# RingMod.net
KiCad netlist of a schematic drawn in EAGLE
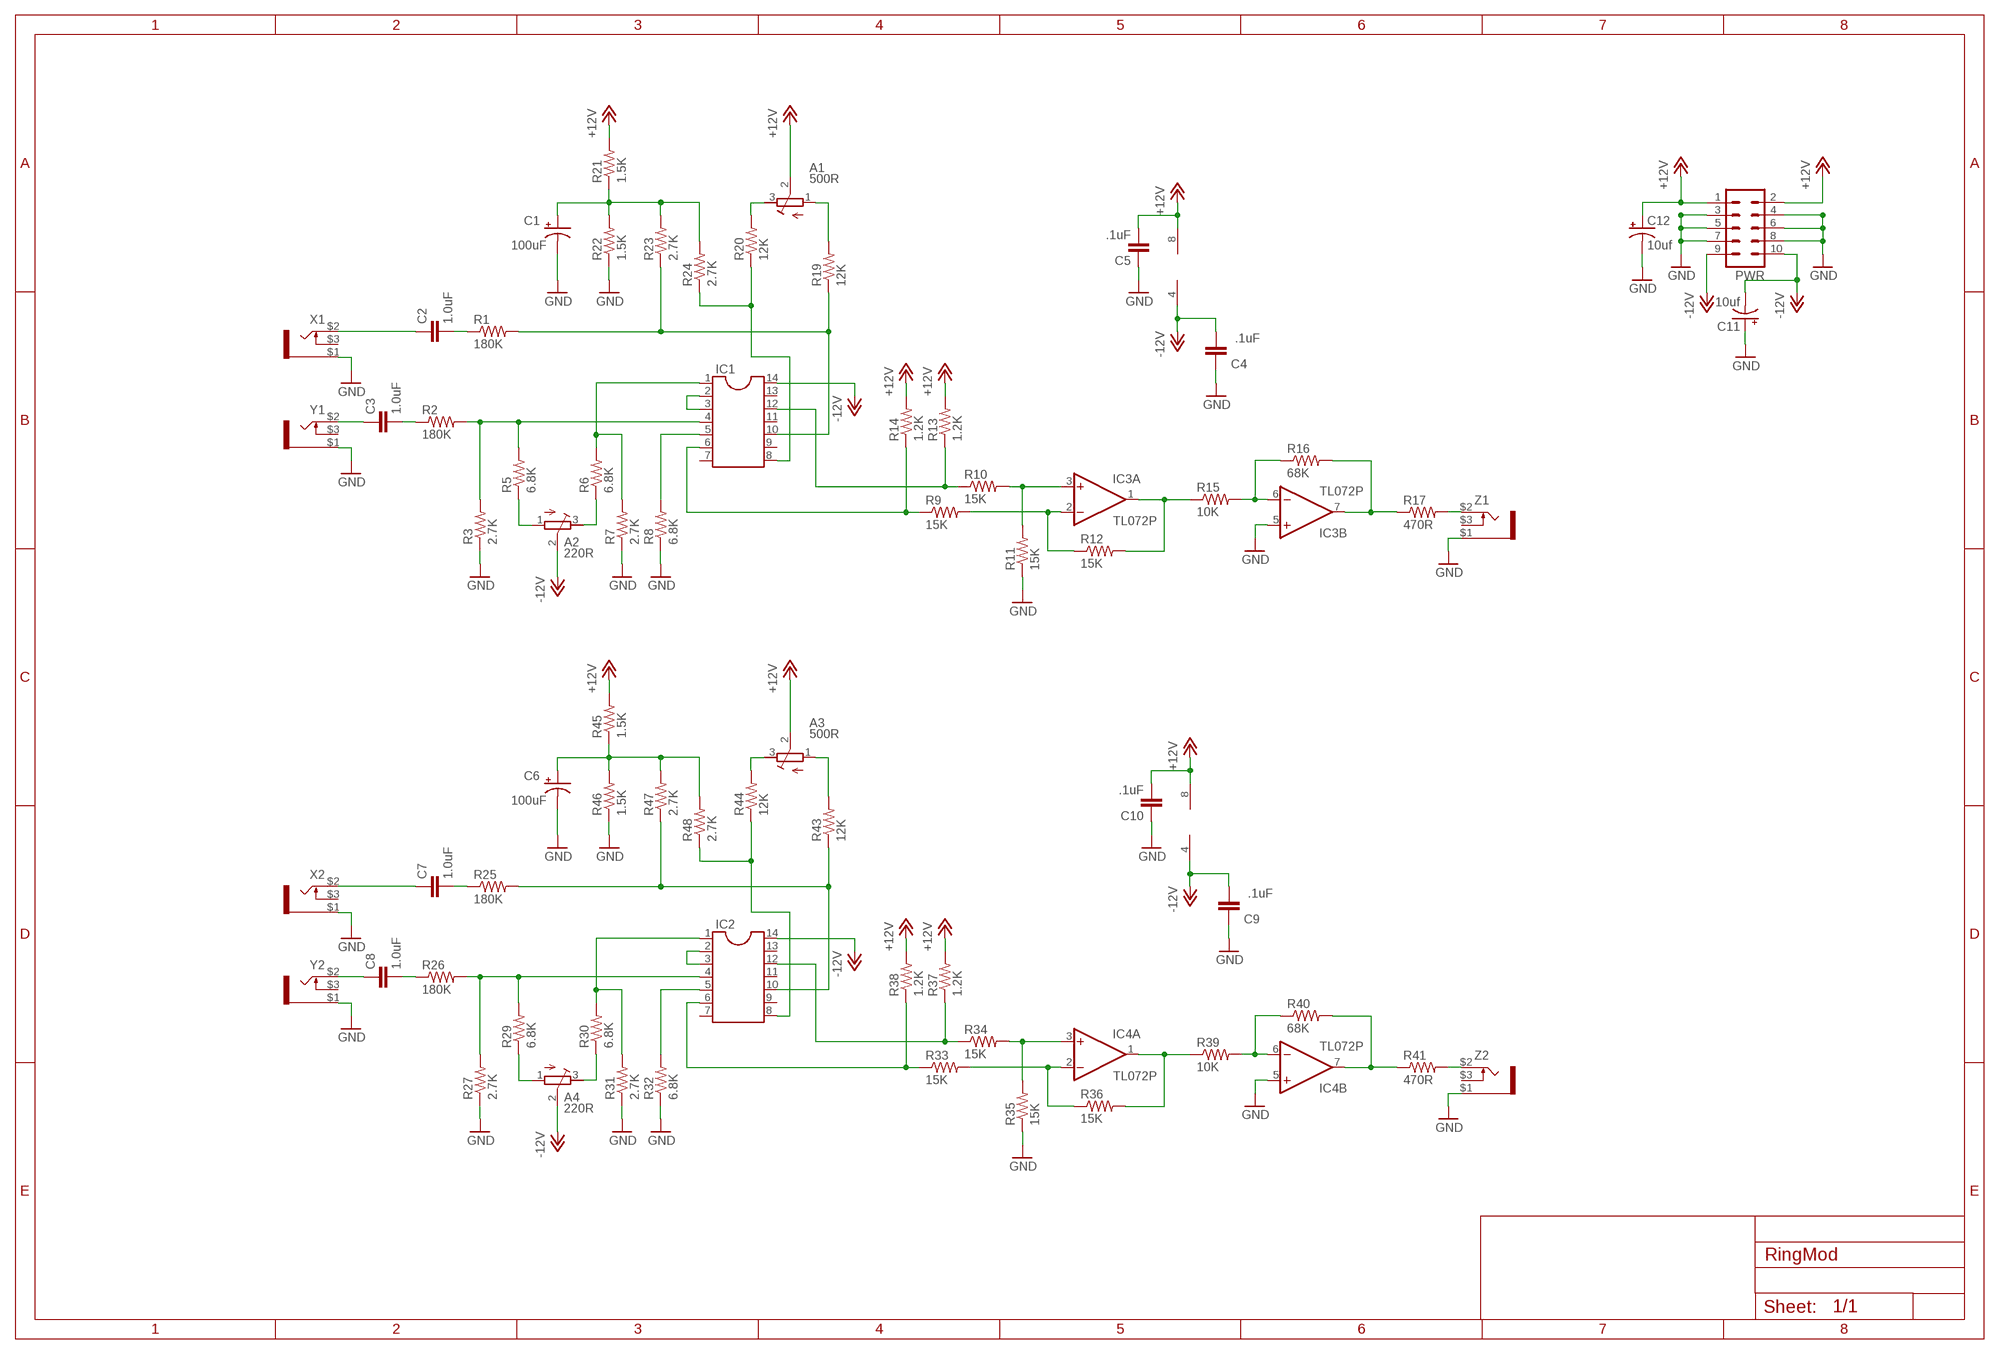
[diagram p0: schematic, sheet 1]

(export (version "E")
  (design (tool "Eeschema 10.0.6"))
  (components
    (comp (ref "A1")
      (value "500R")
      (footprint "eagle-import:RTRIM3296W")
      (libsource (lib "eagle-import") (part "R-TRIMM3296W"))
    )
    (comp (ref "A2")
      (value "220R")
      (footprint "eagle-import:RTRIM3296W")
      (libsource (lib "eagle-import") (part "R-TRIMM3296W"))
    )
    (comp (ref "A3")
      (value "500R")
      (footprint "eagle-import:RTRIM3296W")
      (libsource (lib "eagle-import") (part "R-TRIMM3296W"))
    )
    (comp (ref "A4")
      (value "220R")
      (footprint "eagle-import:RTRIM3296W")
      (libsource (lib "eagle-import") (part "R-TRIMM3296W"))
    )
    (comp (ref "C1")
      (value "100uF")
      (footprint "eagle-import:E2,5-6")
      (libsource (lib "eagle-import") (part "resistor_348_CPOL-USE2.5-6"))
    )
    (comp (ref "C2")
      (value "1.0uF")
      (footprint "eagle-import:C050-024X044")
      (libsource (lib "eagle-import") (part "C-EU050-024X044"))
    )
    (comp (ref "C3")
      (value "1.0uF")
      (footprint "eagle-import:C050-024X044")
      (libsource (lib "eagle-import") (part "C-EU050-024X044"))
    )
    (comp (ref "C4")
      (value ".1uF")
      (footprint "eagle-import:C050-024X044")
      (libsource (lib "eagle-import") (part "C-EU050-024X044"))
    )
    (comp (ref "C5")
      (value ".1uF")
      (footprint "eagle-import:C050-024X044")
      (libsource (lib "eagle-import") (part "C-EU050-024X044"))
    )
    (comp (ref "C6")
      (value "100uF")
      (footprint "eagle-import:E2,5-6")
      (libsource (lib "eagle-import") (part "resistor_348_CPOL-USE2.5-6"))
    )
    (comp (ref "C7")
      (value "1.0uF")
      (footprint "eagle-import:C050-024X044")
      (libsource (lib "eagle-import") (part "C-EU050-024X044"))
    )
    (comp (ref "C8")
      (value "1.0uF")
      (footprint "eagle-import:C050-024X044")
      (libsource (lib "eagle-import") (part "C-EU050-024X044"))
    )
    (comp (ref "C9")
      (value ".1uF")
      (footprint "eagle-import:C050-024X044")
      (libsource (lib "eagle-import") (part "C-EU050-024X044"))
    )
    (comp (ref "C10")
      (value ".1uF")
      (footprint "eagle-import:C050-024X044")
      (libsource (lib "eagle-import") (part "C-EU050-024X044"))
    )
    (comp (ref "C11")
      (value "10uf")
      (footprint "eagle-import:E2,5-5")
      (libsource (lib "eagle-import") (part "CPOL-USE2.5-5"))
    )
    (comp (ref "C12")
      (value "10uf")
      (footprint "eagle-import:E2,5-5")
      (libsource (lib "eagle-import") (part "CPOL-USE2.5-5"))
    )
    (comp (ref "IC1")
      (value "LM1496")
      (footprint "eagle-import:LM1496")
      (libsource (lib "eagle-import") (part "LM1496"))
    )
    (comp (ref "IC2")
      (value "LM1496")
      (footprint "eagle-import:LM1496")
      (libsource (lib "eagle-import") (part "LM1496"))
    )
    (comp (ref "IC3")
      (value "TL072P")
      (footprint "eagle-import:DIL08")
      (libsource (lib "eagle-import") (part "TL072P"))
    )
    (comp (ref "IC4")
      (value "TL072P")
      (footprint "eagle-import:DIL08")
      (libsource (lib "eagle-import") (part "TL072P"))
    )
    (comp (ref "PWR")
      (value "ML10")
      (footprint "eagle-import:ML10")
      (libsource (lib "eagle-import") (part "ML10"))
    )
    (comp (ref "R1")
      (value "180K")
      (footprint "eagle-import:0207_7")
      (libsource (lib "eagle-import") (part "R-US_0207/7"))
    )
    (comp (ref "R2")
      (value "180K")
      (footprint "eagle-import:0207_7")
      (libsource (lib "eagle-import") (part "R-US_0207/7"))
    )
    (comp (ref "R3")
      (value "2.7K")
      (footprint "eagle-import:0207_7")
      (libsource (lib "eagle-import") (part "R-US_0207/7"))
    )
    (comp (ref "R5")
      (value "6.8K")
      (footprint "eagle-import:0207_7")
      (libsource (lib "eagle-import") (part "R-US_0207/7"))
    )
    (comp (ref "R6")
      (value "6.8K")
      (footprint "eagle-import:0207_7")
      (libsource (lib "eagle-import") (part "R-US_0207/7"))
    )
    (comp (ref "R7")
      (value "2.7K")
      (footprint "eagle-import:0207_7")
      (libsource (lib "eagle-import") (part "R-US_0207/7"))
    )
    (comp (ref "R8")
      (value "6.8K")
      (footprint "eagle-import:0207_7")
      (libsource (lib "eagle-import") (part "R-US_0207/7"))
    )
    (comp (ref "R9")
      (value "15K")
      (footprint "eagle-import:0207_7")
      (libsource (lib "eagle-import") (part "R-US_0207/7"))
    )
    (comp (ref "R10")
      (value "15K")
      (footprint "eagle-import:0207_7")
      (libsource (lib "eagle-import") (part "R-US_0207/7"))
    )
    (comp (ref "R11")
      (value "15K")
      (footprint "eagle-import:0207_7")
      (libsource (lib "eagle-import") (part "R-US_0207/7"))
    )
    (comp (ref "R12")
      (value "15K")
      (footprint "eagle-import:0207_7")
      (libsource (lib "eagle-import") (part "R-US_0207/7"))
    )
    (comp (ref "R13")
      (value "1.2K")
      (footprint "eagle-import:0207_7")
      (libsource (lib "eagle-import") (part "R-US_0207/7"))
    )
    (comp (ref "R14")
      (value "1.2K")
      (footprint "eagle-import:0207_7")
      (libsource (lib "eagle-import") (part "R-US_0207/7"))
    )
    (comp (ref "R15")
      (value "10K")
      (footprint "eagle-import:0207_7")
      (libsource (lib "eagle-import") (part "R-US_0207/7"))
    )
    (comp (ref "R16")
      (value "68K")
      (footprint "eagle-import:0207_7")
      (libsource (lib "eagle-import") (part "R-US_0207/7"))
    )
    (comp (ref "R17")
      (value "470R")
      (footprint "eagle-import:0207_7")
      (libsource (lib "eagle-import") (part "R-US_0207/7"))
    )
    (comp (ref "R19")
      (value "12K")
      (footprint "eagle-import:0207_7")
      (libsource (lib "eagle-import") (part "R-US_0207/7"))
    )
    (comp (ref "R20")
      (value "12K")
      (footprint "eagle-import:0207_7")
      (libsource (lib "eagle-import") (part "R-US_0207/7"))
    )
    (comp (ref "R21")
      (value "1.5K")
      (footprint "eagle-import:0207_7")
      (libsource (lib "eagle-import") (part "R-US_0207/7"))
    )
    (comp (ref "R22")
      (value "1.5K")
      (footprint "eagle-import:0207_7")
      (libsource (lib "eagle-import") (part "R-US_0207/7"))
    )
    (comp (ref "R23")
      (value "2.7K")
      (footprint "eagle-import:0207_7")
      (libsource (lib "eagle-import") (part "R-US_0207/7"))
    )
    (comp (ref "R24")
      (value "2.7K")
      (footprint "eagle-import:0207_7")
      (libsource (lib "eagle-import") (part "R-US_0207/7"))
    )
    (comp (ref "R25")
      (value "180K")
      (footprint "eagle-import:0207_7")
      (libsource (lib "eagle-import") (part "R-US_0207/7"))
    )
    (comp (ref "R26")
      (value "180K")
      (footprint "eagle-import:0207_7")
      (libsource (lib "eagle-import") (part "R-US_0207/7"))
    )
    (comp (ref "R27")
      (value "2.7K")
      (footprint "eagle-import:0207_7")
      (libsource (lib "eagle-import") (part "R-US_0207/7"))
    )
    (comp (ref "R29")
      (value "6.8K")
      (footprint "eagle-import:0207_7")
      (libsource (lib "eagle-import") (part "R-US_0207/7"))
    )
    (comp (ref "R30")
      (value "6.8K")
      (footprint "eagle-import:0207_7")
      (libsource (lib "eagle-import") (part "R-US_0207/7"))
    )
    (comp (ref "R31")
      (value "2.7K")
      (footprint "eagle-import:0207_7")
      (libsource (lib "eagle-import") (part "R-US_0207/7"))
    )
    (comp (ref "R32")
      (value "6.8K")
      (footprint "eagle-import:0207_7")
      (libsource (lib "eagle-import") (part "R-US_0207/7"))
    )
    (comp (ref "R33")
      (value "15K")
      (footprint "eagle-import:0207_7")
      (libsource (lib "eagle-import") (part "R-US_0207/7"))
    )
    (comp (ref "R34")
      (value "15K")
      (footprint "eagle-import:0207_7")
      (libsource (lib "eagle-import") (part "R-US_0207/7"))
    )
    (comp (ref "R35")
      (value "15K")
      (footprint "eagle-import:0207_7")
      (libsource (lib "eagle-import") (part "R-US_0207/7"))
    )
    (comp (ref "R36")
      (value "15K")
      (footprint "eagle-import:0207_7")
      (libsource (lib "eagle-import") (part "R-US_0207/7"))
    )
    (comp (ref "R37")
      (value "1.2K")
      (footprint "eagle-import:0207_7")
      (libsource (lib "eagle-import") (part "R-US_0207/7"))
    )
    (comp (ref "R38")
      (value "1.2K")
      (footprint "eagle-import:0207_7")
      (libsource (lib "eagle-import") (part "R-US_0207/7"))
    )
    (comp (ref "R39")
      (value "10K")
      (footprint "eagle-import:0207_7")
      (libsource (lib "eagle-import") (part "R-US_0207/7"))
    )
    (comp (ref "R40")
      (value "68K")
      (footprint "eagle-import:0207_7")
      (libsource (lib "eagle-import") (part "R-US_0207/7"))
    )
    (comp (ref "R41")
      (value "470R")
      (footprint "eagle-import:0207_7")
      (libsource (lib "eagle-import") (part "R-US_0207/7"))
    )
    (comp (ref "R43")
      (value "12K")
      (footprint "eagle-import:0207_7")
      (libsource (lib "eagle-import") (part "R-US_0207/7"))
    )
    (comp (ref "R44")
      (value "12K")
      (footprint "eagle-import:0207_7")
      (libsource (lib "eagle-import") (part "R-US_0207/7"))
    )
    (comp (ref "R45")
      (value "1.5K")
      (footprint "eagle-import:0207_7")
      (libsource (lib "eagle-import") (part "R-US_0207/7"))
    )
    (comp (ref "R46")
      (value "1.5K")
      (footprint "eagle-import:0207_7")
      (libsource (lib "eagle-import") (part "R-US_0207/7"))
    )
    (comp (ref "R47")
      (value "2.7K")
      (footprint "eagle-import:0207_7")
      (libsource (lib "eagle-import") (part "R-US_0207/7"))
    )
    (comp (ref "R48")
      (value "2.7K")
      (footprint "eagle-import:0207_7")
      (libsource (lib "eagle-import") (part "R-US_0207/7"))
    )
    (comp (ref "X1")
      (value "PJ-323PJ-323")
      (footprint "eagle-import:PJ-323")
      (libsource (lib "eagle-import") (part "PJ-323PJ-323"))
    )
    (comp (ref "X2")
      (value "PJ-323PJ-323")
      (footprint "eagle-import:PJ-323")
      (libsource (lib "eagle-import") (part "PJ-323PJ-323"))
    )
    (comp (ref "Y1")
      (value "PJ-323PJ-323")
      (footprint "eagle-import:PJ-323")
      (libsource (lib "eagle-import") (part "PJ-323PJ-323"))
    )
    (comp (ref "Y2")
      (value "PJ-323PJ-323")
      (footprint "eagle-import:PJ-323")
      (libsource (lib "eagle-import") (part "PJ-323PJ-323"))
    )
    (comp (ref "Z1")
      (value "PJ-323PJ-323")
      (footprint "eagle-import:PJ-323")
      (libsource (lib "eagle-import") (part "PJ-323PJ-323"))
    )
    (comp (ref "Z2")
      (value "PJ-323PJ-323")
      (footprint "eagle-import:PJ-323")
      (libsource (lib "eagle-import") (part "PJ-323PJ-323"))
    )
  )
  (nets
    (net (code "1") (name "+12V") (class "Default")
      (node (ref "A1") (pin "2") (pinfunction "S_2") (pintype "passive"))
      (node (ref "A3") (pin "2") (pinfunction "S_2") (pintype "passive"))
      (node (ref "C10") (pin "2") (pinfunction "2_2") (pintype "passive"))
      (node (ref "C12") (pin "+") (pinfunction "+_+") (pintype "passive"))
      (node (ref "C5") (pin "2") (pinfunction "2_2") (pintype "passive"))
      (node (ref "IC3") (pin "8") (pinfunction "V+_8") (pintype "power_in"))
      (node (ref "IC4") (pin "8") (pinfunction "V+_8") (pintype "power_in"))
      (node (ref "PWR") (pin "1") (pinfunction "1_1") (pintype "passive"))
      (node (ref "PWR") (pin "2") (pinfunction "2_2") (pintype "passive"))
      (node (ref "R13") (pin "2") (pinfunction "2_2") (pintype "passive"))
      (node (ref "R14") (pin "2") (pinfunction "2_2") (pintype "passive"))
      (node (ref "R21") (pin "2") (pinfunction "2_2") (pintype "passive"))
      (node (ref "R37") (pin "2") (pinfunction "2_2") (pintype "passive"))
      (node (ref "R38") (pin "2") (pinfunction "2_2") (pintype "passive"))
      (node (ref "R45") (pin "2") (pinfunction "2_2") (pintype "passive"))
    )
    (net (code "2") (name "-12V") (class "Default")
      (node (ref "A2") (pin "2") (pinfunction "S_2") (pintype "passive"))
      (node (ref "A4") (pin "2") (pinfunction "S_2") (pintype "passive"))
      (node (ref "C11") (pin "-") (pinfunction "-_-") (pintype "passive"))
      (node (ref "C4") (pin "2") (pinfunction "2_2") (pintype "passive"))
      (node (ref "C9") (pin "2") (pinfunction "2_2") (pintype "passive"))
      (node (ref "IC1") (pin "14") (pinfunction "14_14") (pintype "passive"))
      (node (ref "IC2") (pin "14") (pinfunction "14_14") (pintype "passive"))
      (node (ref "IC3") (pin "4") (pinfunction "V-_4") (pintype "power_in"))
      (node (ref "IC4") (pin "4") (pinfunction "V-_4") (pintype "power_in"))
      (node (ref "PWR") (pin "10") (pinfunction "10_10") (pintype "passive"))
      (node (ref "PWR") (pin "9") (pinfunction "9_9") (pintype "passive"))
    )
    (net (code "3") (name "GND") (class "Default")
      (node (ref "C1") (pin "-") (pinfunction "-_-") (pintype "passive"))
      (node (ref "C10") (pin "1") (pinfunction "1_1") (pintype "passive"))
      (node (ref "C11") (pin "+") (pinfunction "+_+") (pintype "passive"))
      (node (ref "C12") (pin "-") (pinfunction "-_-") (pintype "passive"))
      (node (ref "C4") (pin "1") (pinfunction "1_1") (pintype "passive"))
      (node (ref "C5") (pin "1") (pinfunction "1_1") (pintype "passive"))
      (node (ref "C6") (pin "-") (pinfunction "-_-") (pintype "passive"))
      (node (ref "C9") (pin "1") (pinfunction "1_1") (pintype "passive"))
      (node (ref "IC3") (pin "5") (pinfunction "+IN_5") (pintype "input"))
      (node (ref "IC4") (pin "5") (pinfunction "+IN_5") (pintype "input"))
      (node (ref "PWR") (pin "3") (pinfunction "3_3") (pintype "passive"))
      (node (ref "PWR") (pin "4") (pinfunction "4_4") (pintype "passive"))
      (node (ref "PWR") (pin "5") (pinfunction "5_5") (pintype "passive"))
      (node (ref "PWR") (pin "6") (pinfunction "6_6") (pintype "passive"))
      (node (ref "PWR") (pin "7") (pinfunction "7_7") (pintype "passive"))
      (node (ref "PWR") (pin "8") (pinfunction "8_8") (pintype "passive"))
      (node (ref "R11") (pin "1") (pinfunction "1_1") (pintype "passive"))
      (node (ref "R22") (pin "1") (pinfunction "1_1") (pintype "passive"))
      (node (ref "R27") (pin "1") (pinfunction "1_1") (pintype "passive"))
      (node (ref "R3") (pin "1") (pinfunction "1_1") (pintype "passive"))
      (node (ref "R31") (pin "1") (pinfunction "1_1") (pintype "passive"))
      (node (ref "R32") (pin "1") (pinfunction "1_1") (pintype "passive"))
      (node (ref "R35") (pin "1") (pinfunction "1_1") (pintype "passive"))
      (node (ref "R46") (pin "1") (pinfunction "1_1") (pintype "passive"))
      (node (ref "R7") (pin "1") (pinfunction "1_1") (pintype "passive"))
      (node (ref "R8") (pin "1") (pinfunction "1_1") (pintype "passive"))
      (node (ref "X1") (pin "$1") (pinfunction "3_$1") (pintype "passive"))
      (node (ref "X2") (pin "$1") (pinfunction "3_$1") (pintype "passive"))
      (node (ref "Y1") (pin "$1") (pinfunction "3_$1") (pintype "passive"))
      (node (ref "Y2") (pin "$1") (pinfunction "3_$1") (pintype "passive"))
      (node (ref "Z1") (pin "$1") (pinfunction "3_$1") (pintype "passive"))
      (node (ref "Z2") (pin "$1") (pinfunction "3_$1") (pintype "passive"))
    )
    (net (code "4") (name "Net-(A1-A)") (class "Default")
      (node (ref "A1") (pin "1") (pinfunction "A_1") (pintype "passive"))
      (node (ref "R19") (pin "2") (pinfunction "2_2") (pintype "passive"))
    )
    (net (code "5") (name "Net-(A1-E)") (class "Default")
      (node (ref "A1") (pin "3") (pinfunction "E_3") (pintype "passive"))
      (node (ref "R20") (pin "2") (pinfunction "2_2") (pintype "passive"))
    )
    (net (code "6") (name "Net-(A2-A)") (class "Default")
      (node (ref "A2") (pin "1") (pinfunction "A_1") (pintype "passive"))
      (node (ref "R5") (pin "1") (pinfunction "1_1") (pintype "passive"))
    )
    (net (code "7") (name "Net-(A2-E)") (class "Default")
      (node (ref "A2") (pin "3") (pinfunction "E_3") (pintype "passive"))
      (node (ref "R6") (pin "1") (pinfunction "1_1") (pintype "passive"))
    )
    (net (code "8") (name "Net-(A3-A)") (class "Default")
      (node (ref "A3") (pin "1") (pinfunction "A_1") (pintype "passive"))
      (node (ref "R43") (pin "2") (pinfunction "2_2") (pintype "passive"))
    )
    (net (code "9") (name "Net-(A3-E)") (class "Default")
      (node (ref "A3") (pin "3") (pinfunction "E_3") (pintype "passive"))
      (node (ref "R44") (pin "2") (pinfunction "2_2") (pintype "passive"))
    )
    (net (code "10") (name "Net-(A4-A)") (class "Default")
      (node (ref "A4") (pin "1") (pinfunction "A_1") (pintype "passive"))
      (node (ref "R29") (pin "1") (pinfunction "1_1") (pintype "passive"))
    )
    (net (code "11") (name "Net-(A4-E)") (class "Default")
      (node (ref "A4") (pin "3") (pinfunction "E_3") (pintype "passive"))
      (node (ref "R30") (pin "1") (pinfunction "1_1") (pintype "passive"))
    )
    (net (code "12") (name "Net-(C1-Pad+)") (class "Default")
      (node (ref "C1") (pin "+") (pinfunction "+_+") (pintype "passive"))
      (node (ref "R21") (pin "1") (pinfunction "1_1") (pintype "passive"))
      (node (ref "R22") (pin "2") (pinfunction "2_2") (pintype "passive"))
      (node (ref "R23") (pin "2") (pinfunction "2_2") (pintype "passive"))
      (node (ref "R24") (pin "2") (pinfunction "2_2") (pintype "passive"))
    )
    (net (code "13") (name "Net-(C2-Pad2)") (class "Default")
      (node (ref "C2") (pin "2") (pinfunction "2_2") (pintype "passive"))
      (node (ref "R1") (pin "1") (pinfunction "1_1") (pintype "passive"))
    )
    (net (code "14") (name "Net-(C3-Pad2)") (class "Default")
      (node (ref "C3") (pin "2") (pinfunction "2_2") (pintype "passive"))
      (node (ref "R2") (pin "1") (pinfunction "1_1") (pintype "passive"))
    )
    (net (code "15") (name "Net-(C6-Pad+)") (class "Default")
      (node (ref "C6") (pin "+") (pinfunction "+_+") (pintype "passive"))
      (node (ref "R45") (pin "1") (pinfunction "1_1") (pintype "passive"))
      (node (ref "R46") (pin "2") (pinfunction "2_2") (pintype "passive"))
      (node (ref "R47") (pin "2") (pinfunction "2_2") (pintype "passive"))
      (node (ref "R48") (pin "2") (pinfunction "2_2") (pintype "passive"))
    )
    (net (code "16") (name "Net-(C7-Pad2)") (class "Default")
      (node (ref "C7") (pin "2") (pinfunction "2_2") (pintype "passive"))
      (node (ref "R25") (pin "1") (pinfunction "1_1") (pintype "passive"))
    )
    (net (code "17") (name "Net-(C8-Pad2)") (class "Default")
      (node (ref "C8") (pin "2") (pinfunction "2_2") (pintype "passive"))
      (node (ref "R26") (pin "1") (pinfunction "1_1") (pintype "passive"))
    )
    (net (code "18") (name "Net-(IC1-Pad1)") (class "Default")
      (node (ref "IC1") (pin "1") (pinfunction "1_1") (pintype "passive"))
      (node (ref "R6") (pin "2") (pinfunction "2_2") (pintype "passive"))
      (node (ref "R7") (pin "2") (pinfunction "2_2") (pintype "passive"))
    )
    (net (code "19") (name "Net-(IC1-Pad2)") (class "Default")
      (node (ref "IC1") (pin "2") (pinfunction "2_2") (pintype "passive"))
      (node (ref "IC1") (pin "3") (pinfunction "3_3") (pintype "passive"))
    )
    (net (code "20") (name "Net-(IC1-Pad4)") (class "Default")
      (node (ref "IC1") (pin "4") (pinfunction "4_4") (pintype "passive"))
      (node (ref "R2") (pin "2") (pinfunction "2_2") (pintype "passive"))
      (node (ref "R3") (pin "2") (pinfunction "2_2") (pintype "passive"))
      (node (ref "R5") (pin "2") (pinfunction "2_2") (pintype "passive"))
    )
    (net (code "21") (name "Net-(IC1-Pad5)") (class "Default")
      (node (ref "IC1") (pin "5") (pinfunction "5_5") (pintype "passive"))
      (node (ref "R8") (pin "2") (pinfunction "2_2") (pintype "passive"))
    )
    (net (code "22") (name "Net-(IC1-Pad6)") (class "Default")
      (node (ref "IC1") (pin "6") (pinfunction "6_6") (pintype "passive"))
      (node (ref "R14") (pin "1") (pinfunction "1_1") (pintype "passive"))
      (node (ref "R9") (pin "1") (pinfunction "1_1") (pintype "passive"))
    )
    (net (code "23") (name "Net-(IC1-Pad8)") (class "Default")
      (node (ref "IC1") (pin "8") (pinfunction "8_8") (pintype "passive"))
      (node (ref "R20") (pin "1") (pinfunction "1_1") (pintype "passive"))
      (node (ref "R24") (pin "1") (pinfunction "1_1") (pintype "passive"))
    )
    (net (code "24") (name "Net-(IC1-Pad10)") (class "Default")
      (node (ref "IC1") (pin "10") (pinfunction "10_10") (pintype "passive"))
      (node (ref "R1") (pin "2") (pinfunction "2_2") (pintype "passive"))
      (node (ref "R19") (pin "1") (pinfunction "1_1") (pintype "passive"))
      (node (ref "R23") (pin "1") (pinfunction "1_1") (pintype "passive"))
    )
    (net (code "25") (name "Net-(IC1-Pad12)") (class "Default")
      (node (ref "IC1") (pin "12") (pinfunction "12_12") (pintype "passive"))
      (node (ref "R10") (pin "1") (pinfunction "1_1") (pintype "passive"))
      (node (ref "R13") (pin "1") (pinfunction "1_1") (pintype "passive"))
    )
    (net (code "26") (name "Net-(IC2-Pad1)") (class "Default")
      (node (ref "IC2") (pin "1") (pinfunction "1_1") (pintype "passive"))
      (node (ref "R30") (pin "2") (pinfunction "2_2") (pintype "passive"))
      (node (ref "R31") (pin "2") (pinfunction "2_2") (pintype "passive"))
    )
    (net (code "27") (name "Net-(IC2-Pad2)") (class "Default")
      (node (ref "IC2") (pin "2") (pinfunction "2_2") (pintype "passive"))
      (node (ref "IC2") (pin "3") (pinfunction "3_3") (pintype "passive"))
    )
    (net (code "28") (name "Net-(IC2-Pad4)") (class "Default")
      (node (ref "IC2") (pin "4") (pinfunction "4_4") (pintype "passive"))
      (node (ref "R26") (pin "2") (pinfunction "2_2") (pintype "passive"))
      (node (ref "R27") (pin "2") (pinfunction "2_2") (pintype "passive"))
      (node (ref "R29") (pin "2") (pinfunction "2_2") (pintype "passive"))
    )
    (net (code "29") (name "Net-(IC2-Pad5)") (class "Default")
      (node (ref "IC2") (pin "5") (pinfunction "5_5") (pintype "passive"))
      (node (ref "R32") (pin "2") (pinfunction "2_2") (pintype "passive"))
    )
    (net (code "30") (name "Net-(IC2-Pad6)") (class "Default")
      (node (ref "IC2") (pin "6") (pinfunction "6_6") (pintype "passive"))
      (node (ref "R33") (pin "1") (pinfunction "1_1") (pintype "passive"))
      (node (ref "R38") (pin "1") (pinfunction "1_1") (pintype "passive"))
    )
    (net (code "31") (name "Net-(IC2-Pad8)") (class "Default")
      (node (ref "IC2") (pin "8") (pinfunction "8_8") (pintype "passive"))
      (node (ref "R44") (pin "1") (pinfunction "1_1") (pintype "passive"))
      (node (ref "R48") (pin "1") (pinfunction "1_1") (pintype "passive"))
    )
    (net (code "32") (name "Net-(IC2-Pad10)") (class "Default")
      (node (ref "IC2") (pin "10") (pinfunction "10_10") (pintype "passive"))
      (node (ref "R25") (pin "2") (pinfunction "2_2") (pintype "passive"))
      (node (ref "R43") (pin "1") (pinfunction "1_1") (pintype "passive"))
      (node (ref "R47") (pin "1") (pinfunction "1_1") (pintype "passive"))
    )
    (net (code "33") (name "Net-(IC2-Pad12)") (class "Default")
      (node (ref "IC2") (pin "12") (pinfunction "12_12") (pintype "passive"))
      (node (ref "R34") (pin "1") (pinfunction "1_1") (pintype "passive"))
      (node (ref "R37") (pin "1") (pinfunction "1_1") (pintype "passive"))
    )
    (net (code "34") (name "Net-(IC3A-+IN)") (class "Default")
      (node (ref "IC3") (pin "3") (pinfunction "+IN_3") (pintype "input"))
      (node (ref "R10") (pin "2") (pinfunction "2_2") (pintype "passive"))
      (node (ref "R11") (pin "2") (pinfunction "2_2") (pintype "passive"))
    )
    (net (code "35") (name "Net-(IC3A--IN)") (class "Default")
      (node (ref "IC3") (pin "2") (pinfunction "-IN_2") (pintype "input"))
      (node (ref "R12") (pin "1") (pinfunction "1_1") (pintype "passive"))
      (node (ref "R9") (pin "2") (pinfunction "2_2") (pintype "passive"))
    )
    (net (code "36") (name "Net-(IC3A-OUT)") (class "Default")
      (node (ref "IC3") (pin "1") (pinfunction "OUT_1") (pintype "output"))
      (node (ref "R12") (pin "2") (pinfunction "2_2") (pintype "passive"))
      (node (ref "R15") (pin "1") (pinfunction "1_1") (pintype "passive"))
    )
    (net (code "37") (name "Net-(IC3B--IN)") (class "Default")
      (node (ref "IC3") (pin "6") (pinfunction "-IN_6") (pintype "input"))
      (node (ref "R15") (pin "2") (pinfunction "2_2") (pintype "passive"))
      (node (ref "R16") (pin "1") (pinfunction "1_1") (pintype "passive"))
    )
    (net (code "38") (name "Net-(IC3B-OUT)") (class "Default")
      (node (ref "IC3") (pin "7") (pinfunction "OUT_7") (pintype "output"))
      (node (ref "R16") (pin "2") (pinfunction "2_2") (pintype "passive"))
      (node (ref "R17") (pin "1") (pinfunction "1_1") (pintype "passive"))
    )
    (net (code "39") (name "Net-(IC4A-+IN)") (class "Default")
      (node (ref "IC4") (pin "3") (pinfunction "+IN_3") (pintype "input"))
      (node (ref "R34") (pin "2") (pinfunction "2_2") (pintype "passive"))
      (node (ref "R35") (pin "2") (pinfunction "2_2") (pintype "passive"))
    )
    (net (code "40") (name "Net-(IC4A--IN)") (class "Default")
      (node (ref "IC4") (pin "2") (pinfunction "-IN_2") (pintype "input"))
      (node (ref "R33") (pin "2") (pinfunction "2_2") (pintype "passive"))
      (node (ref "R36") (pin "1") (pinfunction "1_1") (pintype "passive"))
    )
    (net (code "41") (name "Net-(IC4A-OUT)") (class "Default")
      (node (ref "IC4") (pin "1") (pinfunction "OUT_1") (pintype "output"))
      (node (ref "R36") (pin "2") (pinfunction "2_2") (pintype "passive"))
      (node (ref "R39") (pin "1") (pinfunction "1_1") (pintype "passive"))
    )
    (net (code "42") (name "Net-(IC4B--IN)") (class "Default")
      (node (ref "IC4") (pin "6") (pinfunction "-IN_6") (pintype "input"))
      (node (ref "R39") (pin "2") (pinfunction "2_2") (pintype "passive"))
      (node (ref "R40") (pin "1") (pinfunction "1_1") (pintype "passive"))
    )
    (net (code "43") (name "Net-(IC4B-OUT)") (class "Default")
      (node (ref "IC4") (pin "7") (pinfunction "OUT_7") (pintype "output"))
      (node (ref "R40") (pin "2") (pinfunction "2_2") (pintype "passive"))
      (node (ref "R41") (pin "1") (pinfunction "1_1") (pintype "passive"))
    )
    (net (code "44") (name "Net-(X1-1)") (class "Default")
      (node (ref "C2") (pin "1") (pinfunction "1_1") (pintype "passive"))
      (node (ref "X1") (pin "$2") (pinfunction "1_$2") (pintype "passive"))
    )
    (net (code "45") (name "Net-(X2-1)") (class "Default")
      (node (ref "C7") (pin "1") (pinfunction "1_1") (pintype "passive"))
      (node (ref "X2") (pin "$2") (pinfunction "1_$2") (pintype "passive"))
    )
    (net (code "46") (name "Net-(Y1-1)") (class "Default")
      (node (ref "C3") (pin "1") (pinfunction "1_1") (pintype "passive"))
      (node (ref "Y1") (pin "$2") (pinfunction "1_$2") (pintype "passive"))
    )
    (net (code "47") (name "Net-(Y2-1)") (class "Default")
      (node (ref "C8") (pin "1") (pinfunction "1_1") (pintype "passive"))
      (node (ref "Y2") (pin "$2") (pinfunction "1_$2") (pintype "passive"))
    )
    (net (code "48") (name "Net-(Z1-1)") (class "Default")
      (node (ref "R17") (pin "2") (pinfunction "2_2") (pintype "passive"))
      (node (ref "Z1") (pin "$2") (pinfunction "1_$2") (pintype "passive"))
    )
    (net (code "49") (name "Net-(Z2-1)") (class "Default")
      (node (ref "R41") (pin "2") (pinfunction "2_2") (pintype "passive"))
      (node (ref "Z2") (pin "$2") (pinfunction "1_$2") (pintype "passive"))
    )
    (net (code "50") (name "unconnected-(IC1-Pad7)") (class "Default")
      (node (ref "IC1") (pin "7") (pinfunction "7_7") (pintype "passive"))
    )
    (net (code "51") (name "unconnected-(IC1-Pad9)") (class "Default")
      (node (ref "IC1") (pin "9") (pinfunction "9_9") (pintype "passive"))
    )
    (net (code "52") (name "unconnected-(IC1-Pad11)") (class "Default")
      (node (ref "IC1") (pin "11") (pinfunction "11_11") (pintype "passive"))
    )
    (net (code "53") (name "unconnected-(IC1-Pad13)") (class "Default")
      (node (ref "IC1") (pin "13") (pinfunction "13_13") (pintype "passive"))
    )
    (net (code "54") (name "unconnected-(IC2-Pad7)") (class "Default")
      (node (ref "IC2") (pin "7") (pinfunction "7_7") (pintype "passive"))
    )
    (net (code "55") (name "unconnected-(IC2-Pad9)") (class "Default")
      (node (ref "IC2") (pin "9") (pinfunction "9_9") (pintype "passive"))
    )
    (net (code "56") (name "unconnected-(IC2-Pad11)") (class "Default")
      (node (ref "IC2") (pin "11") (pinfunction "11_11") (pintype "passive"))
    )
    (net (code "57") (name "unconnected-(IC2-Pad13)") (class "Default")
      (node (ref "IC2") (pin "13") (pinfunction "13_13") (pintype "passive"))
    )
    (net (code "58") (name "unconnected-(X1-2-Pad$3)") (class "Default")
      (node (ref "X1") (pin "$3") (pinfunction "2_$3") (pintype "passive"))
    )
    (net (code "59") (name "unconnected-(X2-2-Pad$3)") (class "Default")
      (node (ref "X2") (pin "$3") (pinfunction "2_$3") (pintype "passive"))
    )
    (net (code "60") (name "unconnected-(Y1-2-Pad$3)") (class "Default")
      (node (ref "Y1") (pin "$3") (pinfunction "2_$3") (pintype "passive"))
    )
    (net (code "61") (name "unconnected-(Y2-2-Pad$3)") (class "Default")
      (node (ref "Y2") (pin "$3") (pinfunction "2_$3") (pintype "passive"))
    )
    (net (code "62") (name "unconnected-(Z1-2-Pad$3)") (class "Default")
      (node (ref "Z1") (pin "$3") (pinfunction "2_$3") (pintype "passive"))
    )
    (net (code "63") (name "unconnected-(Z2-2-Pad$3)") (class "Default")
      (node (ref "Z2") (pin "$3") (pinfunction "2_$3") (pintype "passive"))
    )
  )
)
